# core.net
KiCad netlist of a schematic drawn in Altium Designer
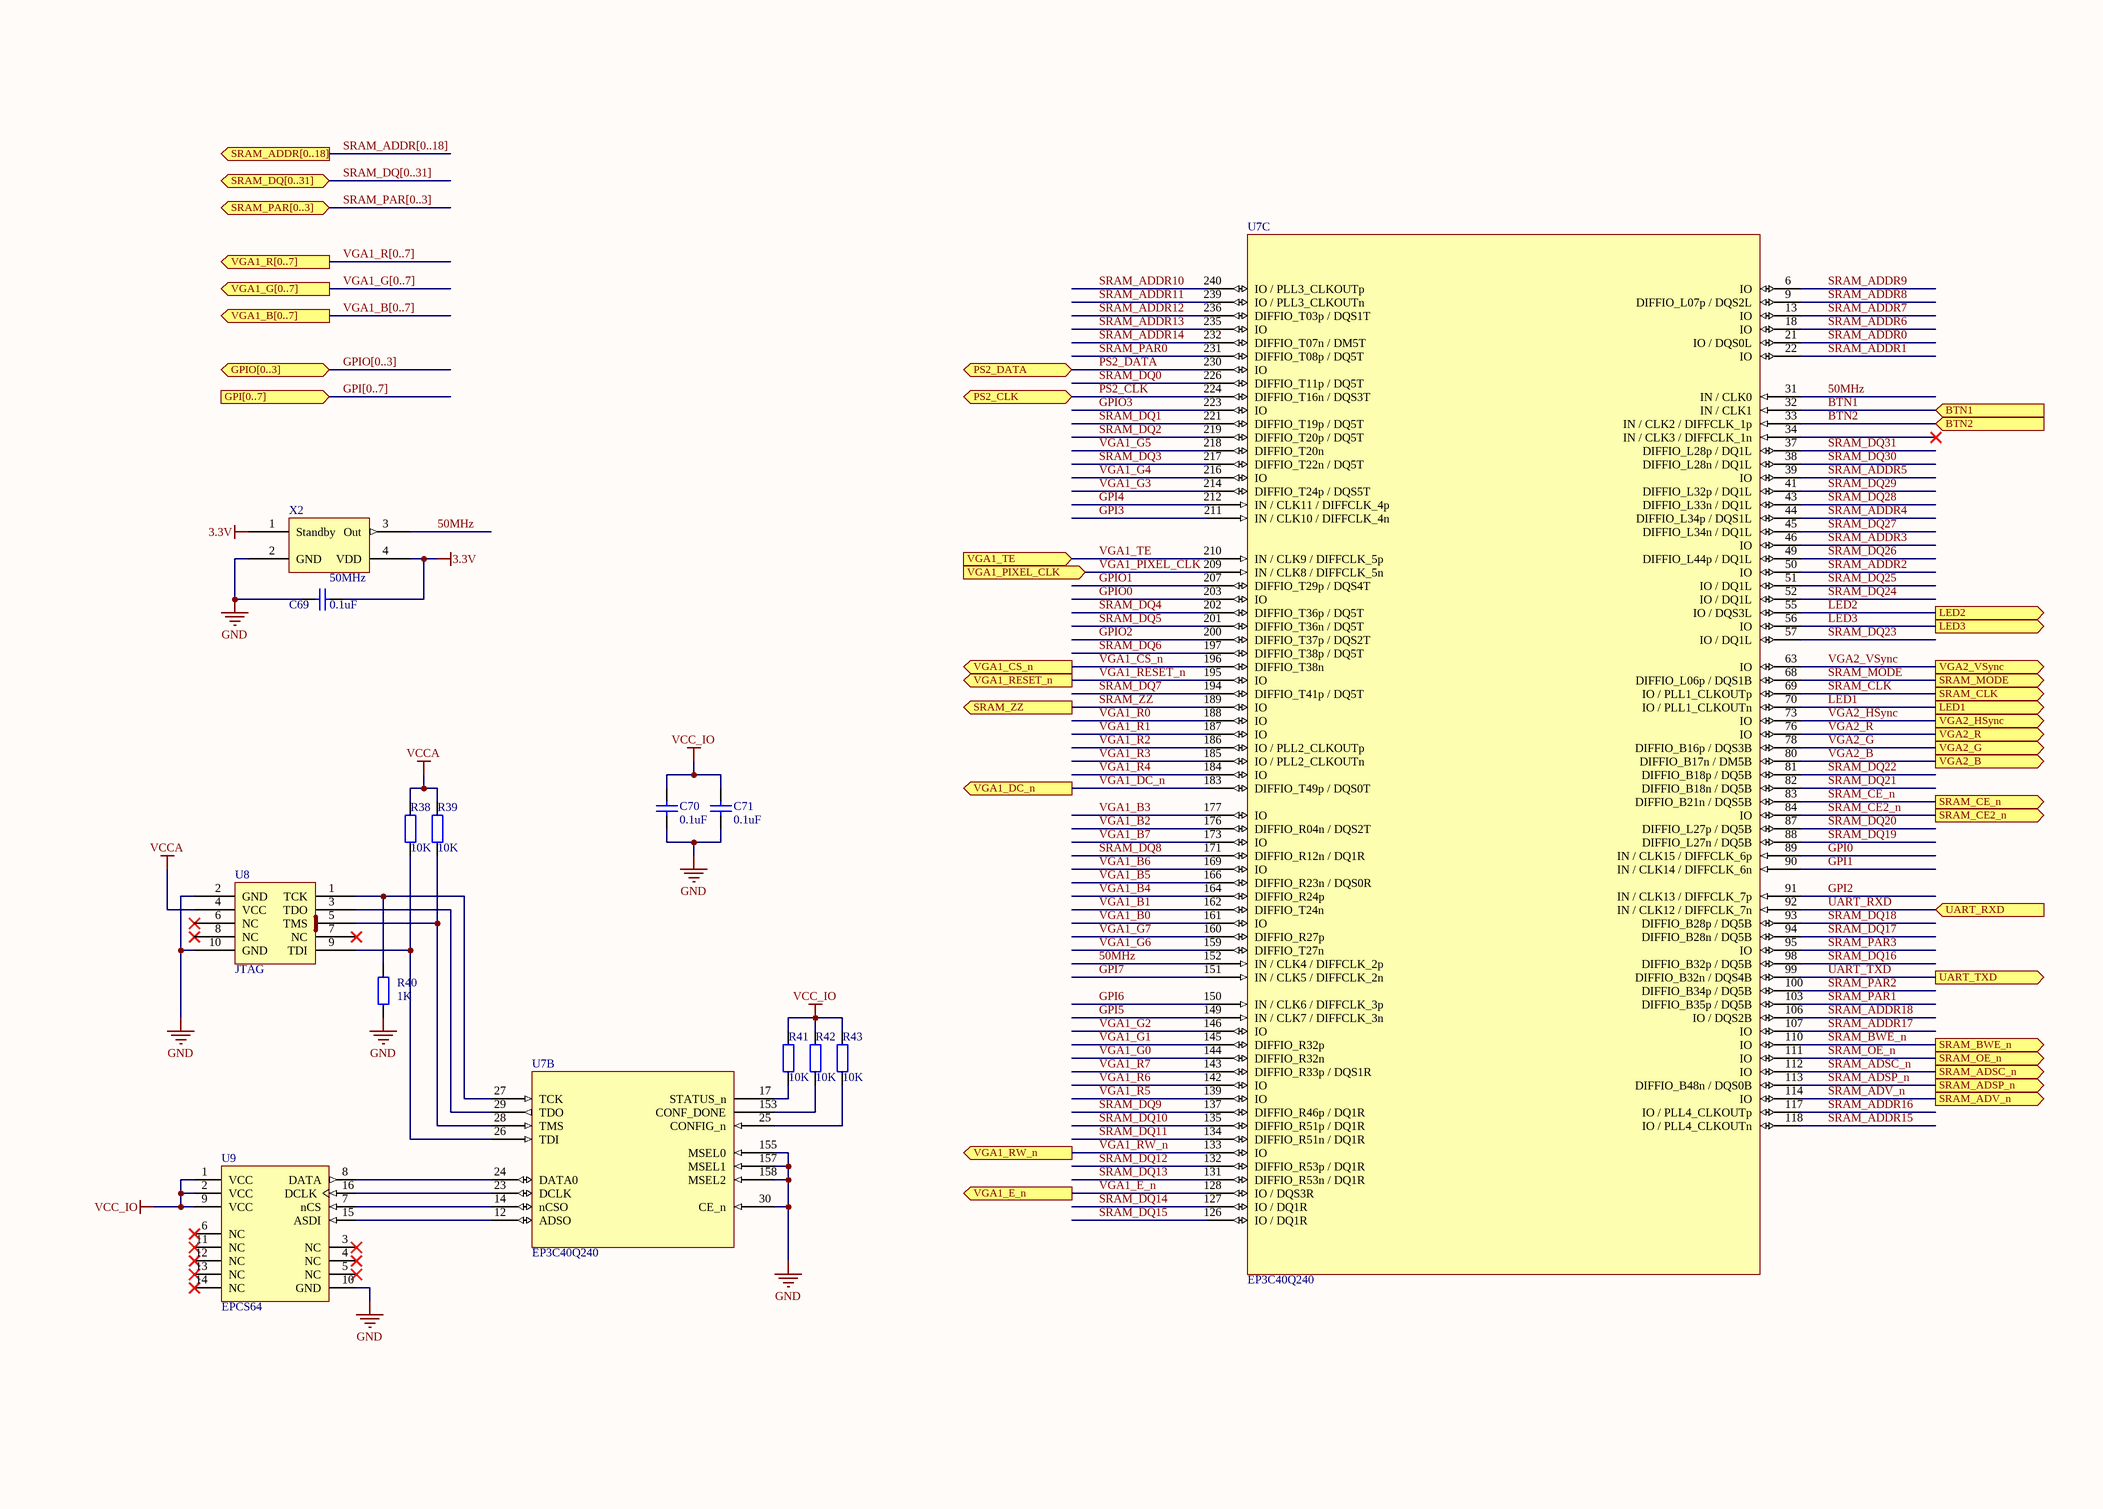
[diagram p0: core.SchDoc]

(export (version "E")
  (design (tool "Eeschema 10.0.6"))
  (components
    (comp (ref "C69")
      (value "0.1uF")
      (footprint "0402")
      (description "Capacitor")
      (fields (field (name "Comment") "Cap") (field (name "PUBLISHER") "Altium Limited"))
      (libsource (lib "Miscellaneous Devices") (part "Cap"))
    )
    (comp (ref "C70")
      (value "0.1uF")
      (footprint "0402")
      (description "Capacitor")
      (fields (field (name "Comment") "Cap") (field (name "PUBLISHER") "Altium Limited"))
      (libsource (lib "Miscellaneous Devices") (part "Cap"))
    )
    (comp (ref "C71")
      (value "0.1uF")
      (footprint "0402")
      (description "Capacitor")
      (fields (field (name "Comment") "Cap") (field (name "PUBLISHER") "Altium Limited"))
      (libsource (lib "Miscellaneous Devices") (part "Cap"))
    )
    (comp (ref "R38")
      (value "10K")
      (footprint "J1-0603")
      (description "Resistor")
      (fields (field (name "Comment") "Res2") (field (name "PUBLISHER") "Altium Limited"))
      (libsource (lib "Miscellaneous Devices") (part "Res2"))
    )
    (comp (ref "R39")
      (value "10K")
      (footprint "J1-0603")
      (description "Resistor")
      (fields (field (name "Comment") "Res2") (field (name "PUBLISHER") "Altium Limited"))
      (libsource (lib "Miscellaneous Devices") (part "Res2"))
    )
    (comp (ref "R40")
      (value "1K")
      (footprint "J1-0603")
      (description "Resistor")
      (fields (field (name "Comment") "Res2") (field (name "PUBLISHER") "Altium Limited"))
      (libsource (lib "") (part "Res2_1"))
    )
    (comp (ref "R41")
      (value "10K")
      (footprint "J1-0603")
      (description "Resistor")
      (fields (field (name "Comment") "Res2") (field (name "PUBLISHER") "Altium Limited"))
      (libsource (lib "Miscellaneous Devices") (part "Res2"))
    )
    (comp (ref "R42")
      (value "10K")
      (footprint "J1-0603")
      (description "Resistor")
      (fields (field (name "Comment") "Res2") (field (name "PUBLISHER") "Altium Limited"))
      (libsource (lib "Miscellaneous Devices") (part "Res2"))
    )
    (comp (ref "R43")
      (value "10K")
      (footprint "J1-0603")
      (description "Resistor")
      (fields (field (name "Comment") "Res2") (field (name "PUBLISHER") "Altium Limited"))
      (libsource (lib "Miscellaneous Devices") (part "Res2"))
    )
    (comp (ref "U7")
      (value "EP3C40Q240")
      (footprint "PQFP240")
      (libsource (lib "FPGA_board") (part "EP3C40Q240"))
    )
    (comp (ref "U8") (value "JTAG") (footprint "JTAG_CONN") (libsource (lib "FPGA_board") (part "JTAG_CONN")))
    (comp (ref "U9")
      (value "EPCS64")
      (footprint "SOIC16")
      (fields (field (name "PUBLISHER") "Altium Limited"))
      (libsource (lib "Altera EPCS Configuration Device") (part "EPCS16SI16N"))
    )
    (comp (ref "X2")
      (value "50MHz")
      (footprint "ASDMB")
      (libsource (lib "FPGA_board") (part "ASDMB-50.000MHZ-LY-T"))
    )
  )
  (nets
    (net (code "1") (name "/50MHz") (class "Default")
      (node (ref "U7") (pin "152") (pinfunction "IN_/_CLK4_/_DIFFCLK_2p_152") (pintype "input"))
      (node (ref "U7") (pin "31") (pinfunction "IN_/_CLK0_31") (pintype "input"))
      (node (ref "X2") (pin "3") (pinfunction "Out_3") (pintype "output"))
    )
    (net (code "2") (name "/BTN1") (class "Default")
      (node (ref "U7") (pin "32") (pinfunction "IN_/_CLK1_32") (pintype "input"))
    )
    (net (code "3") (name "/BTN2") (class "Default")
      (node (ref "U7") (pin "33") (pinfunction "IN_/_CLK2_/_DIFFCLK_1p_33") (pintype "input"))
    )
    (net (code "4") (name "/GPI0") (class "Default")
      (node (ref "U7") (pin "89") (pinfunction "IN_/_CLK15_/_DIFFCLK_6p_89") (pintype "input"))
    )
    (net (code "5") (name "/GPI1") (class "Default")
      (node (ref "U7") (pin "90") (pinfunction "IN_/_CLK14_/_DIFFCLK_6n_90") (pintype "input"))
    )
    (net (code "6") (name "/GPI2") (class "Default")
      (node (ref "U7") (pin "91") (pinfunction "IN_/_CLK13_/_DIFFCLK_7p_91") (pintype "input"))
    )
    (net (code "7") (name "/GPI3") (class "Default")
      (node (ref "U7") (pin "211") (pinfunction "IN_/_CLK10_/_DIFFCLK_4n_211") (pintype "input"))
    )
    (net (code "8") (name "/GPI4") (class "Default")
      (node (ref "U7") (pin "212") (pinfunction "IN_/_CLK11_/_DIFFCLK_4p_212") (pintype "input"))
    )
    (net (code "9") (name "/GPI5") (class "Default")
      (node (ref "U7") (pin "149") (pinfunction "IN_/_CLK7_/_DIFFCLK_3n_149") (pintype "input"))
    )
    (net (code "10") (name "/GPI6") (class "Default")
      (node (ref "U7") (pin "150") (pinfunction "IN_/_CLK6_/_DIFFCLK_3p_150") (pintype "input"))
    )
    (net (code "11") (name "/GPI7") (class "Default")
      (node (ref "U7") (pin "151") (pinfunction "IN_/_CLK5_/_DIFFCLK_2n_151") (pintype "input"))
    )
    (net (code "12") (name "/GPIO0") (class "Default")
      (node (ref "U7") (pin "203") (pinfunction "IO_203") (pintype "bidirectional"))
    )
    (net (code "13") (name "/GPIO1") (class "Default")
      (node (ref "U7") (pin "207") (pinfunction "DIFFIO_T29p_/_DQS4T_207") (pintype "bidirectional"))
    )
    (net (code "14") (name "/GPIO2") (class "Default")
      (node (ref "U7") (pin "200") (pinfunction "DIFFIO_T37p_/_DQS2T_200") (pintype "bidirectional"))
    )
    (net (code "15") (name "/GPIO3") (class "Default")
      (node (ref "U7") (pin "223") (pinfunction "IO_223") (pintype "bidirectional"))
    )
    (net (code "18") (name "/LED1") (class "Default")
      (node (ref "U7") (pin "70") (pinfunction "IO_/_PLL1_CLKOUTn_70") (pintype "bidirectional"))
    )
    (net (code "19") (name "/LED2") (class "Default")
      (node (ref "U7") (pin "55") (pinfunction "IO_/_DQS3L_55") (pintype "bidirectional"))
    )
    (net (code "20") (name "/LED3") (class "Default")
      (node (ref "U7") (pin "56") (pinfunction "IO_56") (pintype "bidirectional"))
    )
    (net (code "21") (name "/PS2_CLK") (class "Default")
      (node (ref "U7") (pin "224") (pinfunction "DIFFIO_T16n_/_DQS3T_224") (pintype "bidirectional"))
    )
    (net (code "22") (name "/PS2_DATA") (class "Default")
      (node (ref "U7") (pin "230") (pinfunction "IO_230") (pintype "bidirectional"))
    )
    (net (code "23") (name "/SRAM_ADDR0") (class "Default")
      (node (ref "U7") (pin "21") (pinfunction "IO_/_DQS0L_21") (pintype "bidirectional"))
    )
    (net (code "24") (name "/SRAM_ADDR1") (class "Default")
      (node (ref "U7") (pin "22") (pinfunction "IO_22") (pintype "bidirectional"))
    )
    (net (code "25") (name "/SRAM_ADDR2") (class "Default")
      (node (ref "U7") (pin "50") (pinfunction "IO_50") (pintype "bidirectional"))
    )
    (net (code "26") (name "/SRAM_ADDR3") (class "Default")
      (node (ref "U7") (pin "46") (pinfunction "IO_46") (pintype "bidirectional"))
    )
    (net (code "27") (name "/SRAM_ADDR4") (class "Default")
      (node (ref "U7") (pin "44") (pinfunction "DIFFIO_L34p_/_DQS1L_44") (pintype "bidirectional"))
    )
    (net (code "28") (name "/SRAM_ADDR5") (class "Default")
      (node (ref "U7") (pin "39") (pinfunction "IO_39") (pintype "bidirectional"))
    )
    (net (code "29") (name "/SRAM_ADDR6") (class "Default")
      (node (ref "U7") (pin "18") (pinfunction "IO_18") (pintype "bidirectional"))
    )
    (net (code "30") (name "/SRAM_ADDR7") (class "Default")
      (node (ref "U7") (pin "13") (pinfunction "IO_13") (pintype "bidirectional"))
    )
    (net (code "31") (name "/SRAM_ADDR8") (class "Default")
      (node (ref "U7") (pin "9") (pinfunction "DIFFIO_L07p_/_DQS2L_9") (pintype "bidirectional"))
    )
    (net (code "32") (name "/SRAM_ADDR9") (class "Default")
      (node (ref "U7") (pin "6") (pinfunction "IO_6") (pintype "bidirectional"))
    )
    (net (code "33") (name "/SRAM_ADDR10") (class "Default")
      (node (ref "U7") (pin "240") (pinfunction "IO_/_PLL3_CLKOUTp_240") (pintype "bidirectional"))
    )
    (net (code "34") (name "/SRAM_ADDR11") (class "Default")
      (node (ref "U7") (pin "239") (pinfunction "IO_/_PLL3_CLKOUTn_239") (pintype "bidirectional"))
    )
    (net (code "35") (name "/SRAM_ADDR12") (class "Default")
      (node (ref "U7") (pin "236") (pinfunction "DIFFIO_T03p_/_DQS1T_236") (pintype "bidirectional"))
    )
    (net (code "36") (name "/SRAM_ADDR13") (class "Default")
      (node (ref "U7") (pin "235") (pinfunction "IO_235") (pintype "bidirectional"))
    )
    (net (code "37") (name "/SRAM_ADDR14") (class "Default")
      (node (ref "U7") (pin "232") (pinfunction "DIFFIO_T07n_/_DM5T_232") (pintype "bidirectional"))
    )
    (net (code "38") (name "/SRAM_ADDR15") (class "Default")
      (node (ref "U7") (pin "118") (pinfunction "IO_/_PLL4_CLKOUTn_118") (pintype "bidirectional"))
    )
    (net (code "39") (name "/SRAM_ADDR16") (class "Default")
      (node (ref "U7") (pin "117") (pinfunction "IO_/_PLL4_CLKOUTp_117") (pintype "bidirectional"))
    )
    (net (code "40") (name "/SRAM_ADDR17") (class "Default")
      (node (ref "U7") (pin "107") (pinfunction "IO_107") (pintype "bidirectional"))
    )
    (net (code "41") (name "/SRAM_ADDR18") (class "Default")
      (node (ref "U7") (pin "106") (pinfunction "IO_/_DQS2B_106") (pintype "bidirectional"))
    )
    (net (code "43") (name "/SRAM_ADSC_n") (class "Default")
      (node (ref "U7") (pin "112") (pinfunction "IO_112") (pintype "bidirectional"))
    )
    (net (code "44") (name "/SRAM_ADSP_n") (class "Default")
      (node (ref "U7") (pin "113") (pinfunction "DIFFIO_B48n_/_DQS0B_113") (pintype "bidirectional"))
    )
    (net (code "45") (name "/SRAM_ADV_n") (class "Default")
      (node (ref "U7") (pin "114") (pinfunction "IO_114") (pintype "bidirectional"))
    )
    (net (code "46") (name "/SRAM_BWE_n") (class "Default")
      (node (ref "U7") (pin "110") (pinfunction "IO_110") (pintype "bidirectional"))
    )
    (net (code "47") (name "/SRAM_CE2_n") (class "Default")
      (node (ref "U7") (pin "84") (pinfunction "IO_84") (pintype "bidirectional"))
    )
    (net (code "48") (name "/SRAM_CE_n") (class "Default")
      (node (ref "U7") (pin "83") (pinfunction "DIFFIO_B21n_/_DQS5B_83") (pintype "bidirectional"))
    )
    (net (code "49") (name "/SRAM_CLK") (class "Default")
      (node (ref "U7") (pin "69") (pinfunction "IO_/_PLL1_CLKOUTp_69") (pintype "bidirectional"))
    )
    (net (code "50") (name "/SRAM_DQ0") (class "Default")
      (node (ref "U7") (pin "226") (pinfunction "DIFFIO_T11p_/_DQ5T_226") (pintype "bidirectional"))
    )
    (net (code "51") (name "/SRAM_DQ1") (class "Default")
      (node (ref "U7") (pin "221") (pinfunction "DIFFIO_T19p_/_DQ5T_221") (pintype "bidirectional"))
    )
    (net (code "52") (name "/SRAM_DQ2") (class "Default")
      (node (ref "U7") (pin "219") (pinfunction "DIFFIO_T20p_/_DQ5T_219") (pintype "bidirectional"))
    )
    (net (code "53") (name "/SRAM_DQ3") (class "Default")
      (node (ref "U7") (pin "217") (pinfunction "DIFFIO_T22n_/_DQ5T_217") (pintype "bidirectional"))
    )
    (net (code "54") (name "/SRAM_DQ4") (class "Default")
      (node (ref "U7") (pin "202") (pinfunction "DIFFIO_T36p_/_DQ5T_202") (pintype "bidirectional"))
    )
    (net (code "55") (name "/SRAM_DQ5") (class "Default")
      (node (ref "U7") (pin "201") (pinfunction "DIFFIO_T36n_/_DQ5T_201") (pintype "bidirectional"))
    )
    (net (code "56") (name "/SRAM_DQ6") (class "Default")
      (node (ref "U7") (pin "197") (pinfunction "DIFFIO_T38p_/_DQ5T_197") (pintype "bidirectional"))
    )
    (net (code "57") (name "/SRAM_DQ7") (class "Default")
      (node (ref "U7") (pin "194") (pinfunction "DIFFIO_T41p_/_DQ5T_194") (pintype "bidirectional"))
    )
    (net (code "58") (name "/SRAM_DQ8") (class "Default")
      (node (ref "U7") (pin "171") (pinfunction "DIFFIO_R12n_/_DQ1R_171") (pintype "bidirectional"))
    )
    (net (code "59") (name "/SRAM_DQ9") (class "Default")
      (node (ref "U7") (pin "137") (pinfunction "DIFFIO_R46p_/_DQ1R_137") (pintype "bidirectional"))
    )
    (net (code "60") (name "/SRAM_DQ10") (class "Default")
      (node (ref "U7") (pin "135") (pinfunction "DIFFIO_R51p_/_DQ1R_135") (pintype "bidirectional"))
    )
    (net (code "61") (name "/SRAM_DQ11") (class "Default")
      (node (ref "U7") (pin "134") (pinfunction "DIFFIO_R51n_/_DQ1R_134") (pintype "bidirectional"))
    )
    (net (code "62") (name "/SRAM_DQ12") (class "Default")
      (node (ref "U7") (pin "132") (pinfunction "DIFFIO_R53p_/_DQ1R_132") (pintype "bidirectional"))
    )
    (net (code "63") (name "/SRAM_DQ13") (class "Default")
      (node (ref "U7") (pin "131") (pinfunction "DIFFIO_R53n_/_DQ1R_131") (pintype "bidirectional"))
    )
    (net (code "64") (name "/SRAM_DQ14") (class "Default")
      (node (ref "U7") (pin "127") (pinfunction "IO_/_DQ1R_127") (pintype "bidirectional"))
    )
    (net (code "65") (name "/SRAM_DQ15") (class "Default")
      (node (ref "U7") (pin "126") (pinfunction "IO_/_DQ1R_126") (pintype "bidirectional"))
    )
    (net (code "66") (name "/SRAM_DQ16") (class "Default")
      (node (ref "U7") (pin "98") (pinfunction "DIFFIO_B32p_/_DQ5B_98") (pintype "bidirectional"))
    )
    (net (code "67") (name "/SRAM_DQ17") (class "Default")
      (node (ref "U7") (pin "94") (pinfunction "DIFFIO_B28n_/_DQ5B_94") (pintype "bidirectional"))
    )
    (net (code "68") (name "/SRAM_DQ18") (class "Default")
      (node (ref "U7") (pin "93") (pinfunction "DIFFIO_B28p_/_DQ5B_93") (pintype "bidirectional"))
    )
    (net (code "69") (name "/SRAM_DQ19") (class "Default")
      (node (ref "U7") (pin "88") (pinfunction "DIFFIO_L27n_/_DQ5B_88") (pintype "bidirectional"))
    )
    (net (code "70") (name "/SRAM_DQ20") (class "Default")
      (node (ref "U7") (pin "87") (pinfunction "DIFFIO_L27p_/_DQ5B_87") (pintype "bidirectional"))
    )
    (net (code "71") (name "/SRAM_DQ21") (class "Default")
      (node (ref "U7") (pin "82") (pinfunction "DIFFIO_B18n_/_DQ5B_82") (pintype "bidirectional"))
    )
    (net (code "72") (name "/SRAM_DQ22") (class "Default")
      (node (ref "U7") (pin "81") (pinfunction "DIFFIO_B18p_/_DQ5B_81") (pintype "bidirectional"))
    )
    (net (code "73") (name "/SRAM_DQ23") (class "Default")
      (node (ref "U7") (pin "57") (pinfunction "IO_/_DQ1L_57") (pintype "bidirectional"))
    )
    (net (code "74") (name "/SRAM_DQ24") (class "Default")
      (node (ref "U7") (pin "52") (pinfunction "IO_/_DQ1L_52") (pintype "bidirectional"))
    )
    (net (code "75") (name "/SRAM_DQ25") (class "Default")
      (node (ref "U7") (pin "51") (pinfunction "IO_/_DQ1L_51") (pintype "bidirectional"))
    )
    (net (code "76") (name "/SRAM_DQ26") (class "Default")
      (node (ref "U7") (pin "49") (pinfunction "DIFFIO_L44p_/_DQ1L_49") (pintype "bidirectional"))
    )
    (net (code "77") (name "/SRAM_DQ27") (class "Default")
      (node (ref "U7") (pin "45") (pinfunction "DIFFIO_L34n_/_DQ1L_45") (pintype "bidirectional"))
    )
    (net (code "78") (name "/SRAM_DQ28") (class "Default")
      (node (ref "U7") (pin "43") (pinfunction "DIFFIO_L33n_/_DQ1L_43") (pintype "bidirectional"))
    )
    (net (code "79") (name "/SRAM_DQ29") (class "Default")
      (node (ref "U7") (pin "41") (pinfunction "DIFFIO_L32p_/_DQ1L_41") (pintype "bidirectional"))
    )
    (net (code "80") (name "/SRAM_DQ30") (class "Default")
      (node (ref "U7") (pin "38") (pinfunction "DIFFIO_L28n_/_DQ1L_38") (pintype "bidirectional"))
    )
    (net (code "81") (name "/SRAM_DQ31") (class "Default")
      (node (ref "U7") (pin "37") (pinfunction "DIFFIO_L28p_/_DQ1L_37") (pintype "bidirectional"))
    )
    (net (code "83") (name "/SRAM_MODE") (class "Default")
      (node (ref "U7") (pin "68") (pinfunction "DIFFIO_L06p_/_DQS1B_68") (pintype "bidirectional"))
    )
    (net (code "84") (name "/SRAM_OE_n") (class "Default")
      (node (ref "U7") (pin "111") (pinfunction "IO_111") (pintype "bidirectional"))
    )
    (net (code "85") (name "/SRAM_PAR0") (class "Default")
      (node (ref "U7") (pin "231") (pinfunction "DIFFIO_T08p_/_DQ5T_231") (pintype "bidirectional"))
    )
    (net (code "86") (name "/SRAM_PAR1") (class "Default")
      (node (ref "U7") (pin "103") (pinfunction "DIFFIO_B35p_/_DQ5B_103") (pintype "bidirectional"))
    )
    (net (code "87") (name "/SRAM_PAR2") (class "Default")
      (node (ref "U7") (pin "100") (pinfunction "DIFFIO_B34p_/_DQ5B_100") (pintype "bidirectional"))
    )
    (net (code "88") (name "/SRAM_PAR3") (class "Default")
      (node (ref "U7") (pin "95") (pinfunction "IO_95") (pintype "bidirectional"))
    )
    (net (code "90") (name "/SRAM_ZZ") (class "Default")
      (node (ref "U7") (pin "189") (pinfunction "IO_189") (pintype "bidirectional"))
    )
    (net (code "91") (name "/UART_RXD") (class "Default")
      (node (ref "U7") (pin "92") (pinfunction "IN_/_CLK12_/_DIFFCLK_7n_92") (pintype "input"))
    )
    (net (code "92") (name "/UART_TXD") (class "Default")
      (node (ref "U7") (pin "99") (pinfunction "DIFFIO_B32n_/_DQS4B_99") (pintype "bidirectional"))
    )
    (net (code "93") (name "/VGA1_B0") (class "Default")
      (node (ref "U7") (pin "161") (pinfunction "IO_161") (pintype "bidirectional"))
    )
    (net (code "94") (name "/VGA1_B1") (class "Default")
      (node (ref "U7") (pin "162") (pinfunction "DIFFIO_T24n_162") (pintype "bidirectional"))
    )
    (net (code "95") (name "/VGA1_B2") (class "Default")
      (node (ref "U7") (pin "176") (pinfunction "DIFFIO_R04n_/_DQS2T_176") (pintype "bidirectional"))
    )
    (net (code "96") (name "/VGA1_B3") (class "Default")
      (node (ref "U7") (pin "177") (pinfunction "IO_177") (pintype "bidirectional"))
    )
    (net (code "97") (name "/VGA1_B4") (class "Default")
      (node (ref "U7") (pin "164") (pinfunction "DIFFIO_R24p_164") (pintype "bidirectional"))
    )
    (net (code "98") (name "/VGA1_B5") (class "Default")
      (node (ref "U7") (pin "166") (pinfunction "DIFFIO_R23n_/_DQS0R_166") (pintype "bidirectional"))
    )
    (net (code "99") (name "/VGA1_B6") (class "Default")
      (node (ref "U7") (pin "169") (pinfunction "IO_169") (pintype "bidirectional"))
    )
    (net (code "100") (name "/VGA1_B7") (class "Default")
      (node (ref "U7") (pin "173") (pinfunction "IO_173") (pintype "bidirectional"))
    )
    (net (code "102") (name "/VGA1_CS_n") (class "Default")
      (node (ref "U7") (pin "196") (pinfunction "DIFFIO_T38n_196") (pintype "bidirectional"))
    )
    (net (code "103") (name "/VGA1_DC_n") (class "Default")
      (node (ref "U7") (pin "183") (pinfunction "DIFFIO_T49p_/_DQS0T_183") (pintype "bidirectional"))
    )
    (net (code "104") (name "/VGA1_E_n") (class "Default")
      (node (ref "U7") (pin "128") (pinfunction "IO_/_DQS3R_128") (pintype "bidirectional"))
    )
    (net (code "105") (name "/VGA1_G0") (class "Default")
      (node (ref "U7") (pin "144") (pinfunction "DIFFIO_R32n_144") (pintype "bidirectional"))
    )
    (net (code "106") (name "/VGA1_G1") (class "Default")
      (node (ref "U7") (pin "145") (pinfunction "DIFFIO_R32p_145") (pintype "bidirectional"))
    )
    (net (code "107") (name "/VGA1_G2") (class "Default")
      (node (ref "U7") (pin "146") (pinfunction "IO_146") (pintype "bidirectional"))
    )
    (net (code "108") (name "/VGA1_G3") (class "Default")
      (node (ref "U7") (pin "214") (pinfunction "DIFFIO_T24p_/_DQS5T_214") (pintype "bidirectional"))
    )
    (net (code "109") (name "/VGA1_G4") (class "Default")
      (node (ref "U7") (pin "216") (pinfunction "IO_216") (pintype "bidirectional"))
    )
    (net (code "110") (name "/VGA1_G5") (class "Default")
      (node (ref "U7") (pin "218") (pinfunction "DIFFIO_T20n_218") (pintype "bidirectional"))
    )
    (net (code "111") (name "/VGA1_G6") (class "Default")
      (node (ref "U7") (pin "159") (pinfunction "DIFFIO_T27n_159") (pintype "bidirectional"))
    )
    (net (code "112") (name "/VGA1_G7") (class "Default")
      (node (ref "U7") (pin "160") (pinfunction "DIFFIO_R27p_160") (pintype "bidirectional"))
    )
    (net (code "114") (name "/VGA1_PIXEL_CLK") (class "Default")
      (node (ref "U7") (pin "209") (pinfunction "IN_/_CLK8_/_DIFFCLK_5n_209") (pintype "input"))
    )
    (net (code "115") (name "/VGA1_R0") (class "Default")
      (node (ref "U7") (pin "188") (pinfunction "IO_188") (pintype "bidirectional"))
    )
    (net (code "116") (name "/VGA1_R1") (class "Default")
      (node (ref "U7") (pin "187") (pinfunction "IO_187") (pintype "bidirectional"))
    )
    (net (code "117") (name "/VGA1_R2") (class "Default")
      (node (ref "U7") (pin "186") (pinfunction "IO_/_PLL2_CLKOUTp_186") (pintype "bidirectional"))
    )
    (net (code "118") (name "/VGA1_R3") (class "Default")
      (node (ref "U7") (pin "185") (pinfunction "IO_/_PLL2_CLKOUTn_185") (pintype "bidirectional"))
    )
    (net (code "119") (name "/VGA1_R4") (class "Default")
      (node (ref "U7") (pin "184") (pinfunction "IO_184") (pintype "bidirectional"))
    )
    (net (code "120") (name "/VGA1_R5") (class "Default")
      (node (ref "U7") (pin "139") (pinfunction "IO_139") (pintype "bidirectional"))
    )
    (net (code "121") (name "/VGA1_R6") (class "Default")
      (node (ref "U7") (pin "142") (pinfunction "IO_142") (pintype "bidirectional"))
    )
    (net (code "122") (name "/VGA1_R7") (class "Default")
      (node (ref "U7") (pin "143") (pinfunction "DIFFIO_R33p_/_DQS1R_143") (pintype "bidirectional"))
    )
    (net (code "123") (name "/VGA1_RESET_n") (class "Default")
      (node (ref "U7") (pin "195") (pinfunction "IO_195") (pintype "bidirectional"))
    )
    (net (code "124") (name "/VGA1_RW_n") (class "Default")
      (node (ref "U7") (pin "133") (pinfunction "IO_133") (pintype "bidirectional"))
    )
    (net (code "126") (name "/VGA1_TE") (class "Default")
      (node (ref "U7") (pin "210") (pinfunction "IN_/_CLK9_/_DIFFCLK_5p_210") (pintype "input"))
    )
    (net (code "127") (name "/VGA2_B") (class "Default")
      (node (ref "U7") (pin "80") (pinfunction "DIFFIO_B17n_/_DM5B_80") (pintype "bidirectional"))
    )
    (net (code "128") (name "/VGA2_G") (class "Default")
      (node (ref "U7") (pin "78") (pinfunction "DIFFIO_B16p_/_DQS3B_78") (pintype "bidirectional"))
    )
    (net (code "129") (name "/VGA2_HSync") (class "Default")
      (node (ref "U7") (pin "73") (pinfunction "IO_73") (pintype "bidirectional"))
    )
    (net (code "130") (name "/VGA2_R") (class "Default")
      (node (ref "U7") (pin "76") (pinfunction "IO_76") (pintype "bidirectional"))
    )
    (net (code "131") (name "/VGA2_VSync") (class "Default")
      (node (ref "U7") (pin "63") (pinfunction "IO_63") (pintype "bidirectional"))
    )
    (net (code "132") (name "3.3V") (class "Default")
      (node (ref "C69") (pin "2") (pinfunction "2_2") (pintype "passive"))
      (node (ref "X2") (pin "1") (pinfunction "Standby_1") (pintype "passive"))
      (node (ref "X2") (pin "4") (pinfunction "VDD_4") (pintype "power_in"))
    )
    (net (code "133") (name "GND") (class "Default")
      (node (ref "C69") (pin "1") (pinfunction "1_1") (pintype "passive"))
      (node (ref "C70") (pin "1") (pinfunction "1_1") (pintype "passive"))
      (node (ref "C71") (pin "1") (pinfunction "1_1") (pintype "passive"))
      (node (ref "R40") (pin "1") (pinfunction "1_1") (pintype "passive"))
      (node (ref "U7") (pin "155") (pinfunction "MSEL0_155") (pintype "input"))
      (node (ref "U7") (pin "157") (pinfunction "MSEL1_157") (pintype "input"))
      (node (ref "U7") (pin "158") (pinfunction "MSEL2_158") (pintype "input"))
      (node (ref "U7") (pin "30") (pinfunction "CE_n_30") (pintype "input"))
      (node (ref "U8") (pin "10") (pinfunction "GND_10") (pintype "passive"))
      (node (ref "U8") (pin "2") (pinfunction "GND_2") (pintype "passive"))
      (node (ref "U9") (pin "10") (pinfunction "GND_10") (pintype "power_in"))
      (node (ref "X2") (pin "2") (pinfunction "GND_2") (pintype "power_in"))
    )
    (net (code "134") (name "Net-(U7B-ADSO)") (class "Default")
      (node (ref "U7") (pin "12") (pinfunction "ADSO_12") (pintype "bidirectional"))
      (node (ref "U9") (pin "15") (pinfunction "ASDI_15") (pintype "input"))
    )
    (net (code "135") (name "Net-(U7B-CONFIG_n)") (class "Default")
      (node (ref "R43") (pin "2") (pinfunction "2_2") (pintype "passive"))
      (node (ref "U7") (pin "25") (pinfunction "CONFIG_n_25") (pintype "input"))
    )
    (net (code "136") (name "Net-(U7B-CONF_DONE)") (class "Default")
      (node (ref "R42") (pin "2") (pinfunction "2_2") (pintype "passive"))
      (node (ref "U7") (pin "153") (pinfunction "CONF_DONE_153") (pintype "open_collector"))
    )
    (net (code "137") (name "Net-(U7B-DATA0)") (class "Default")
      (node (ref "U7") (pin "24") (pinfunction "DATA0_24") (pintype "bidirectional"))
      (node (ref "U9") (pin "8") (pinfunction "DATA_8") (pintype "output"))
    )
    (net (code "138") (name "Net-(U7B-DCLK)") (class "Default")
      (node (ref "U7") (pin "23") (pinfunction "DCLK_23") (pintype "bidirectional"))
      (node (ref "U9") (pin "16") (pinfunction "DCLK_16") (pintype "input"))
    )
    (net (code "139") (name "Net-(U7B-STATUS_n)") (class "Default")
      (node (ref "R41") (pin "2") (pinfunction "2_2") (pintype "passive"))
      (node (ref "U7") (pin "17") (pinfunction "STATUS_n_17") (pintype "open_collector"))
    )
    (net (code "140") (name "Net-(U7B-TCK)") (class "Default")
      (node (ref "R40") (pin "2") (pinfunction "2_2") (pintype "passive"))
      (node (ref "U7") (pin "27") (pinfunction "TCK_27") (pintype "input"))
      (node (ref "U8") (pin "1") (pinfunction "TCK_1") (pintype "passive"))
    )
    (net (code "141") (name "Net-(U7B-TDI)") (class "Default")
      (node (ref "R38") (pin "2") (pinfunction "2_2") (pintype "passive"))
      (node (ref "U7") (pin "26") (pinfunction "TDI_26") (pintype "input"))
      (node (ref "U8") (pin "9") (pinfunction "TDI_9") (pintype "passive"))
    )
    (net (code "142") (name "Net-(U7B-TDO)") (class "Default")
      (node (ref "U7") (pin "29") (pinfunction "TDO_29") (pintype "output"))
      (node (ref "U8") (pin "3") (pinfunction "TDO_3") (pintype "passive"))
    )
    (net (code "143") (name "Net-(U7B-TMS)") (class "Default")
      (node (ref "R39") (pin "2") (pinfunction "2_2") (pintype "passive"))
      (node (ref "U7") (pin "28") (pinfunction "TMS_28") (pintype "input"))
      (node (ref "U8") (pin "5") (pinfunction "TMS_5") (pintype "passive"))
    )
    (net (code "144") (name "Net-(U7B-nCSO)") (class "Default")
      (node (ref "U7") (pin "14") (pinfunction "nCSO_14") (pintype "bidirectional"))
      (node (ref "U9") (pin "7") (pinfunction "nCS_7") (pintype "input"))
    )
    (net (code "145") (name "VCCA") (class "Default")
      (node (ref "R38") (pin "1") (pinfunction "1_1") (pintype "passive"))
      (node (ref "R39") (pin "1") (pinfunction "1_1") (pintype "passive"))
      (node (ref "U8") (pin "4") (pinfunction "VCC_4") (pintype "passive"))
    )
    (net (code "146") (name "VCC_IO") (class "Default")
      (node (ref "C70") (pin "2") (pinfunction "2_2") (pintype "passive"))
      (node (ref "C71") (pin "2") (pinfunction "2_2") (pintype "passive"))
      (node (ref "R41") (pin "1") (pinfunction "1_1") (pintype "passive"))
      (node (ref "R42") (pin "1") (pinfunction "1_1") (pintype "passive"))
      (node (ref "R43") (pin "1") (pinfunction "1_1") (pintype "passive"))
      (node (ref "U9") (pin "1") (pinfunction "VCC_1") (pintype "power_in"))
      (node (ref "U9") (pin "2") (pinfunction "VCC_2") (pintype "power_in"))
      (node (ref "U9") (pin "9") (pinfunction "VCC_9") (pintype "power_in"))
    )
    (net (code "147") (name "unconnected-(U7C-IN_{slash}_CLK3_{slash}_DIFFCLK_1n-Pad34)") (class "Default")
      (node (ref "U7") (pin "34") (pinfunction "IN_/_CLK3_/_DIFFCLK_1n_34") (pintype "input+no_connect"))
    )
    (net (code "148") (name "unconnected-(U8-NC-Pad6)") (class "Default")
      (node (ref "U8") (pin "6") (pinfunction "NC_6") (pintype "passive+no_connect"))
    )
    (net (code "149") (name "unconnected-(U8-NC-Pad7)") (class "Default")
      (node (ref "U8") (pin "7") (pinfunction "NC_7") (pintype "passive+no_connect"))
    )
    (net (code "150") (name "unconnected-(U8-NC-Pad8)") (class "Default")
      (node (ref "U8") (pin "8") (pinfunction "NC_8") (pintype "passive+no_connect"))
    )
    (net (code "151") (name "unconnected-(U9-NC-Pad3)") (class "Default")
      (node (ref "U9") (pin "3") (pinfunction "NC_3") (pintype "passive+no_connect"))
    )
    (net (code "152") (name "unconnected-(U9-NC-Pad4)") (class "Default")
      (node (ref "U9") (pin "4") (pinfunction "NC_4") (pintype "passive+no_connect"))
    )
    (net (code "153") (name "unconnected-(U9-NC-Pad5)") (class "Default")
      (node (ref "U9") (pin "5") (pinfunction "NC_5") (pintype "passive+no_connect"))
    )
    (net (code "154") (name "unconnected-(U9-NC-Pad6)") (class "Default")
      (node (ref "U9") (pin "6") (pinfunction "NC_6") (pintype "passive+no_connect"))
    )
    (net (code "155") (name "unconnected-(U9-NC-Pad11)") (class "Default")
      (node (ref "U9") (pin "11") (pinfunction "NC_11") (pintype "passive+no_connect"))
    )
    (net (code "156") (name "unconnected-(U9-NC-Pad12)") (class "Default")
      (node (ref "U9") (pin "12") (pinfunction "NC_12") (pintype "passive+no_connect"))
    )
    (net (code "157") (name "unconnected-(U9-NC-Pad13)") (class "Default")
      (node (ref "U9") (pin "13") (pinfunction "NC_13") (pintype "passive+no_connect"))
    )
    (net (code "158") (name "unconnected-(U9-NC-Pad14)") (class "Default")
      (node (ref "U9") (pin "14") (pinfunction "NC_14") (pintype "passive+no_connect"))
    )
  )
)
